# Power_Connections.net
KiCad netlist of a schematic drawn in Altium Designer
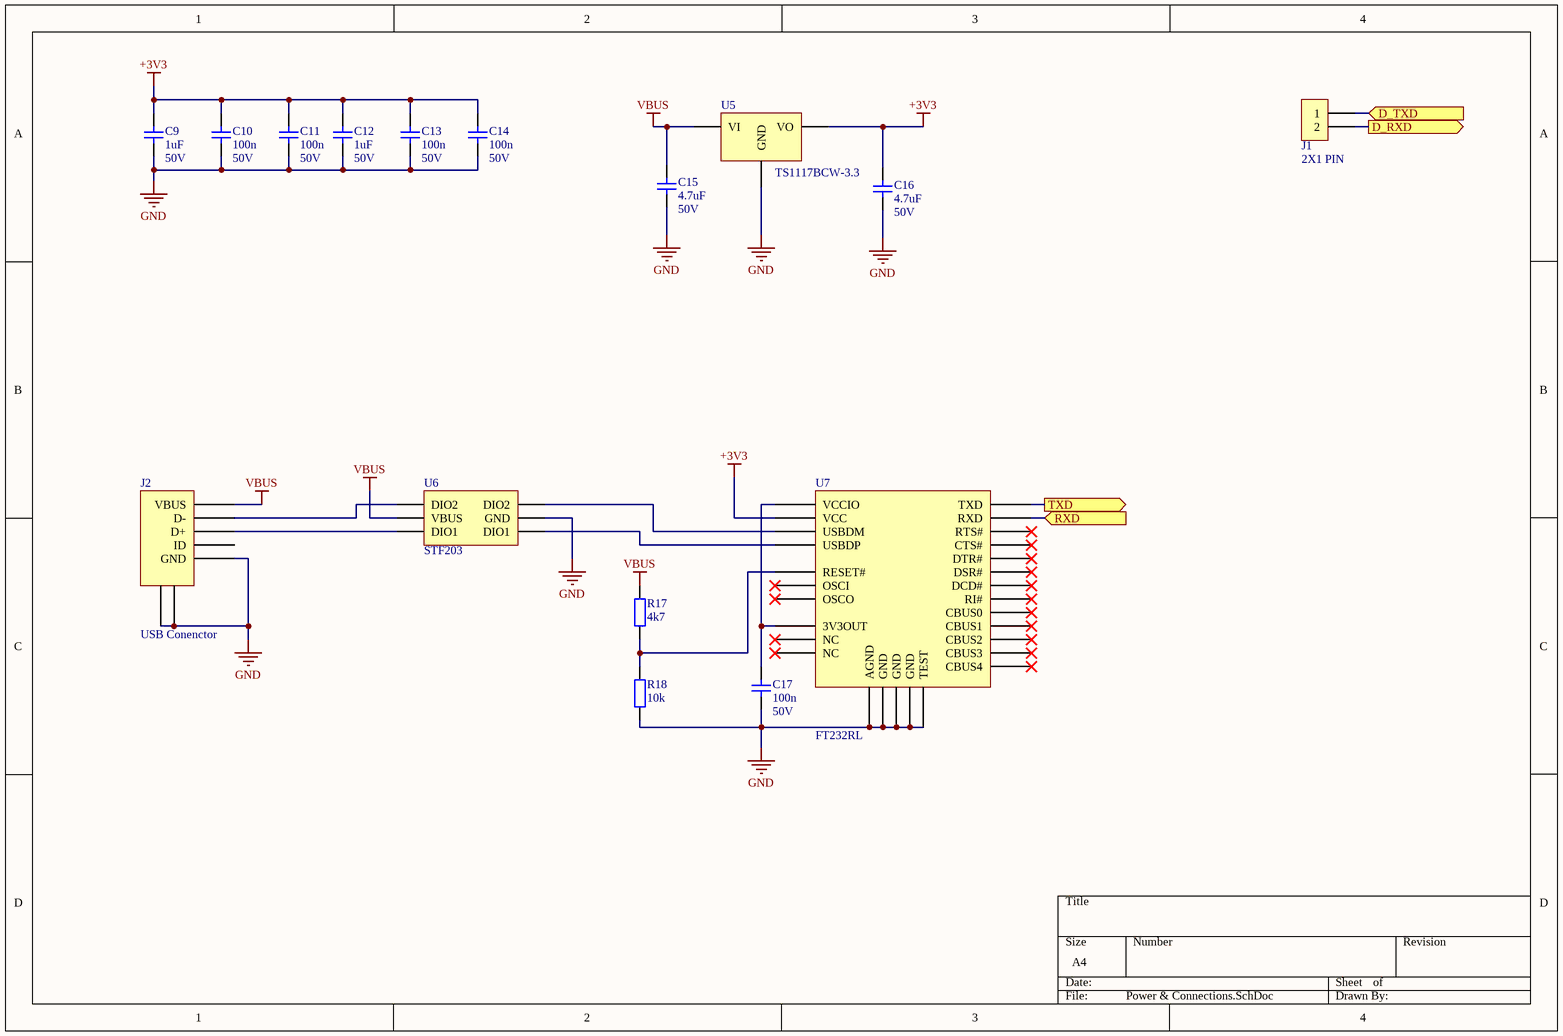
[diagram p0: Power & Connections.SchDoc]

(export (version "E")
  (design (tool "Eeschema 10.0.6"))
  (components
    (comp (ref "C9")
      (value "1uF")
      (footprint "C1206")
      (description "Capacitor")
      (fields (field (name "VOLTAGE RATING") "50V") (field (name "Comment") "CAP"))
      (libsource (lib "Turbine_Lib") (part "CAP"))
    )
    (comp (ref "C10")
      (value "100n")
      (footprint "C1206")
      (description "Capacitor")
      (fields (field (name "VOLTAGE RATING") "50V") (field (name "Comment") "CAP"))
      (libsource (lib "Turbine_Lib") (part "CAP"))
    )
    (comp (ref "C11")
      (value "100n")
      (footprint "C1206")
      (description "Capacitor")
      (fields (field (name "VOLTAGE RATING") "50V") (field (name "Comment") "CAP"))
      (libsource (lib "Turbine_Lib") (part "CAP"))
    )
    (comp (ref "C12")
      (value "1uF")
      (footprint "C1206")
      (description "Capacitor")
      (fields (field (name "VOLTAGE RATING") "50V") (field (name "Comment") "CAP"))
      (libsource (lib "Turbine_Lib") (part "CAP"))
    )
    (comp (ref "C13")
      (value "100n")
      (footprint "C1206")
      (description "Capacitor")
      (fields (field (name "VOLTAGE RATING") "50V") (field (name "Comment") "CAP"))
      (libsource (lib "Turbine_Lib") (part "CAP"))
    )
    (comp (ref "C14")
      (value "100n")
      (footprint "C1206")
      (description "Capacitor")
      (fields (field (name "VOLTAGE RATING") "50V") (field (name "Comment") "CAP"))
      (libsource (lib "Turbine_Lib") (part "CAP"))
    )
    (comp (ref "C15")
      (value "4.7uF")
      (footprint "C1206")
      (description "Capacitor")
      (fields (field (name "VOLTAGE RATING") "50V") (field (name "Comment") "CAP"))
      (libsource (lib "Turbine_Lib") (part "CAP"))
    )
    (comp (ref "C16")
      (value "4.7uF")
      (footprint "C1206")
      (description "Capacitor")
      (fields (field (name "VOLTAGE RATING") "50V") (field (name "Comment") "CAP"))
      (libsource (lib "Turbine_Lib") (part "CAP"))
    )
    (comp (ref "C17")
      (value "100n")
      (footprint "C1206")
      (description "Capacitor")
      (fields (field (name "VOLTAGE RATING") "50V") (field (name "Comment") "CAP"))
      (libsource (lib "Turbine_Lib") (part "CAP"))
    )
    (comp (ref "J1")
      (value "2X1 PIN")
      (footprint "2X1PINHEAD")
      (description "Pin Header 2x1")
      (libsource (lib "Turbine_Lib") (part "2X1 PIN"))
    )
    (comp (ref "J2")
      (value "USB Conenctor")
      (footprint "USB_MINI")
      (description "USB connector")
      (libsource (lib "Turbine_Lib") (part "USB"))
    )
    (comp (ref "R17")
      (value "4k7")
      (footprint "R1206")
      (description "1206 Resistor")
      (fields (field (name "Comment") "1206"))
      (libsource (lib "Turbine_Lib") (part "RES"))
    )
    (comp (ref "R18")
      (value "10k")
      (footprint "R1206")
      (description "1206 Resistor")
      (fields (field (name "Comment") "1206"))
      (libsource (lib "Turbine_Lib") (part "RES"))
    )
    (comp (ref "U5")
      (value "TS1117BCW-3.3")
      (footprint "SOT-223")
      (description "TAIWAN SEMICONDUCTOR - TS1117BCW-3.3 - LDO VOLTAGE REG, 0.8A, 12V, SOT223-3")
      (fields (field (name "MANUFACTURER") "TAIWAN SEMICONDUCTOR"))
      (libsource (lib "Turbine_Lib") (part "TS1117BCW-3.3"))
    )
    (comp (ref "U6")
      (value "STF203")
      (footprint "SOT23-6")
      (description "STF203 - IC, FILTER, USB, ESD PROTECT, SOT236")
      (libsource (lib "Turbine_Lib") (part "STF203"))
    )
    (comp (ref "U7")
      (value "FT232RL")
      (footprint "SSOP28")
      (description "USB-UART Bridge FTDI device")
      (fields (field (name "MANUFACTURER") "FTDI") (field (name "MANUFACTURER PART NUMBER") "FT232RL-REEL"))
      (libsource (lib "Turbine_Lib") (part "FT232RL"))
    )
  )
  (nets
    (net (code "1") (name "+3V3") (class "Default")
      (node (ref "C10") (pin "1") (pinfunction "1_1") (pintype "passive"))
      (node (ref "C11") (pin "1") (pinfunction "1_1") (pintype "passive"))
      (node (ref "C12") (pin "1") (pinfunction "1_1") (pintype "passive"))
      (node (ref "C13") (pin "1") (pinfunction "1_1") (pintype "passive"))
      (node (ref "C14") (pin "1") (pinfunction "1_1") (pintype "passive"))
      (node (ref "C16") (pin "1") (pinfunction "1_1") (pintype "passive"))
      (node (ref "C9") (pin "1") (pinfunction "1_1") (pintype "passive"))
      (node (ref "U5") (pin "2") (pinfunction "VO_2") (pintype "passive"))
      (node (ref "U7") (pin "20") (pinfunction "VCC_20") (pintype "passive"))
    )
    (net (code "2") (name "/D_RXD") (class "Default")
      (node (ref "J1") (pin "2") (pinfunction "2_2") (pintype "passive"))
    )
    (net (code "3") (name "/D_TXD") (class "Default")
      (node (ref "J1") (pin "1") (pinfunction "1_1") (pintype "passive"))
    )
    (net (code "4") (name "/RXD") (class "Default")
      (node (ref "U7") (pin "5") (pinfunction "RXD_5") (pintype "passive"))
    )
    (net (code "5") (name "/TXD") (class "Default")
      (node (ref "U7") (pin "1") (pinfunction "TXD_1") (pintype "passive"))
    )
    (net (code "6") (name "GND") (class "Default")
      (node (ref "C10") (pin "2") (pinfunction "2_2") (pintype "passive"))
      (node (ref "C11") (pin "2") (pinfunction "2_2") (pintype "passive"))
      (node (ref "C12") (pin "2") (pinfunction "2_2") (pintype "passive"))
      (node (ref "C13") (pin "2") (pinfunction "2_2") (pintype "passive"))
      (node (ref "C14") (pin "2") (pinfunction "2_2") (pintype "passive"))
      (node (ref "C15") (pin "2") (pinfunction "2_2") (pintype "passive"))
      (node (ref "C16") (pin "2") (pinfunction "2_2") (pintype "passive"))
      (node (ref "C17") (pin "2") (pinfunction "2_2") (pintype "passive"))
      (node (ref "C9") (pin "2") (pinfunction "2_2") (pintype "passive"))
      (node (ref "J2") (pin "5") (pinfunction "GND_5") (pintype "passive"))
      (node (ref "J2") (pin "6") (pinfunction "SHIELD_6") (pintype "passive"))
      (node (ref "J2") (pin "7") (pinfunction "SHIELD_7") (pintype "passive"))
      (node (ref "R18") (pin "2") (pinfunction "2_2") (pintype "passive"))
      (node (ref "U5") (pin "1") (pinfunction "GND_1") (pintype "passive"))
      (node (ref "U6") (pin "2") (pinfunction "GND_2") (pintype "passive"))
      (node (ref "U7") (pin "18") (pinfunction "GND_18") (pintype "passive"))
      (node (ref "U7") (pin "21") (pinfunction "GND_21") (pintype "passive"))
      (node (ref "U7") (pin "25") (pinfunction "AGND_25") (pintype "passive"))
      (node (ref "U7") (pin "26") (pinfunction "TEST_26") (pintype "passive"))
      (node (ref "U7") (pin "7") (pinfunction "GND_7") (pintype "passive"))
    )
    (net (code "7") (name "Net-(J2-D+)") (class "Default")
      (node (ref "J2") (pin "3") (pinfunction "D+_3") (pintype "passive"))
      (node (ref "U6") (pin "6") (pinfunction "DIO1_6") (pintype "passive"))
    )
    (net (code "8") (name "Net-(J2-D-)") (class "Default")
      (node (ref "J2") (pin "2") (pinfunction "D-_2") (pintype "passive"))
      (node (ref "U6") (pin "4") (pinfunction "DIO2_4") (pintype "passive"))
    )
    (net (code "9") (name "Net-(U7-3V3OUT)") (class "Default")
      (node (ref "C17") (pin "1") (pinfunction "1_1") (pintype "passive"))
      (node (ref "U7") (pin "17") (pinfunction "3V3OUT_17") (pintype "passive"))
      (node (ref "U7") (pin "4") (pinfunction "VCCIO_4") (pintype "passive"))
    )
    (net (code "10") (name "Net-(U7-RESET#)") (class "Default")
      (node (ref "R17") (pin "2") (pinfunction "2_2") (pintype "passive"))
      (node (ref "R18") (pin "1") (pinfunction "1_1") (pintype "passive"))
      (node (ref "U7") (pin "19") (pinfunction "RESET#_19") (pintype "passive"))
    )
    (net (code "11") (name "Net-(U7-USBDM)") (class "Default")
      (node (ref "U6") (pin "3") (pinfunction "DIO2_3") (pintype "passive"))
      (node (ref "U7") (pin "16") (pinfunction "USBDM_16") (pintype "passive"))
    )
    (net (code "12") (name "Net-(U7-USBDP)") (class "Default")
      (node (ref "U6") (pin "1") (pinfunction "DIO1_1") (pintype "passive"))
      (node (ref "U7") (pin "15") (pinfunction "USBDP_15") (pintype "passive"))
    )
    (net (code "13") (name "VBUS") (class "Default")
      (node (ref "C15") (pin "1") (pinfunction "1_1") (pintype "passive"))
      (node (ref "J2") (pin "1") (pinfunction "VBUS_1") (pintype "passive"))
      (node (ref "R17") (pin "1") (pinfunction "1_1") (pintype "passive"))
      (node (ref "U5") (pin "3") (pinfunction "VI_3") (pintype "passive"))
      (node (ref "U6") (pin "5") (pinfunction "VBUS_5") (pintype "passive"))
    )
    (net (code "14") (name "unconnected-(J2-ID-Pad4)") (class "Default")
      (node (ref "J2") (pin "4") (pinfunction "ID_4") (pintype "passive"))
    )
    (net (code "15") (name "unconnected-(U7-CBUS0-Pad23)") (class "Default")
      (node (ref "U7") (pin "23") (pinfunction "CBUS0_23") (pintype "passive+no_connect"))
    )
    (net (code "16") (name "unconnected-(U7-CBUS1-Pad22)") (class "Default")
      (node (ref "U7") (pin "22") (pinfunction "CBUS1_22") (pintype "passive+no_connect"))
    )
    (net (code "17") (name "unconnected-(U7-CBUS2-Pad13)") (class "Default")
      (node (ref "U7") (pin "13") (pinfunction "CBUS2_13") (pintype "passive+no_connect"))
    )
    (net (code "18") (name "unconnected-(U7-CBUS3-Pad14)") (class "Default")
      (node (ref "U7") (pin "14") (pinfunction "CBUS3_14") (pintype "passive+no_connect"))
    )
    (net (code "19") (name "unconnected-(U7-CBUS4-Pad12)") (class "Default")
      (node (ref "U7") (pin "12") (pinfunction "CBUS4_12") (pintype "passive+no_connect"))
    )
    (net (code "20") (name "unconnected-(U7-CTS#-Pad11)") (class "Default")
      (node (ref "U7") (pin "11") (pinfunction "CTS#_11") (pintype "passive+no_connect"))
    )
    (net (code "21") (name "unconnected-(U7-DCD#-Pad10)") (class "Default")
      (node (ref "U7") (pin "10") (pinfunction "DCD#_10") (pintype "passive+no_connect"))
    )
    (net (code "22") (name "unconnected-(U7-DSR#-Pad9)") (class "Default")
      (node (ref "U7") (pin "9") (pinfunction "DSR#_9") (pintype "passive+no_connect"))
    )
    (net (code "23") (name "unconnected-(U7-DTR#-Pad2)") (class "Default")
      (node (ref "U7") (pin "2") (pinfunction "DTR#_2") (pintype "passive+no_connect"))
    )
    (net (code "24") (name "unconnected-(U7-NC-Pad8)") (class "Default")
      (node (ref "U7") (pin "8") (pinfunction "NC_8") (pintype "passive+no_connect"))
    )
    (net (code "25") (name "unconnected-(U7-NC-Pad24)") (class "Default")
      (node (ref "U7") (pin "24") (pinfunction "NC_24") (pintype "passive+no_connect"))
    )
    (net (code "26") (name "unconnected-(U7-OSCI-Pad27)") (class "Default")
      (node (ref "U7") (pin "27") (pinfunction "OSCI_27") (pintype "passive+no_connect"))
    )
    (net (code "27") (name "unconnected-(U7-OSCO-Pad28)") (class "Default")
      (node (ref "U7") (pin "28") (pinfunction "OSCO_28") (pintype "passive+no_connect"))
    )
    (net (code "28") (name "unconnected-(U7-RI#-Pad6)") (class "Default")
      (node (ref "U7") (pin "6") (pinfunction "RI#_6") (pintype "passive+no_connect"))
    )
    (net (code "29") (name "unconnected-(U7-RTS#-Pad3)") (class "Default")
      (node (ref "U7") (pin "3") (pinfunction "RTS#_3") (pintype "passive+no_connect"))
    )
  )
)
